# EBS_2020.net
KiCad netlist of a schematic drawn in Altium Designer
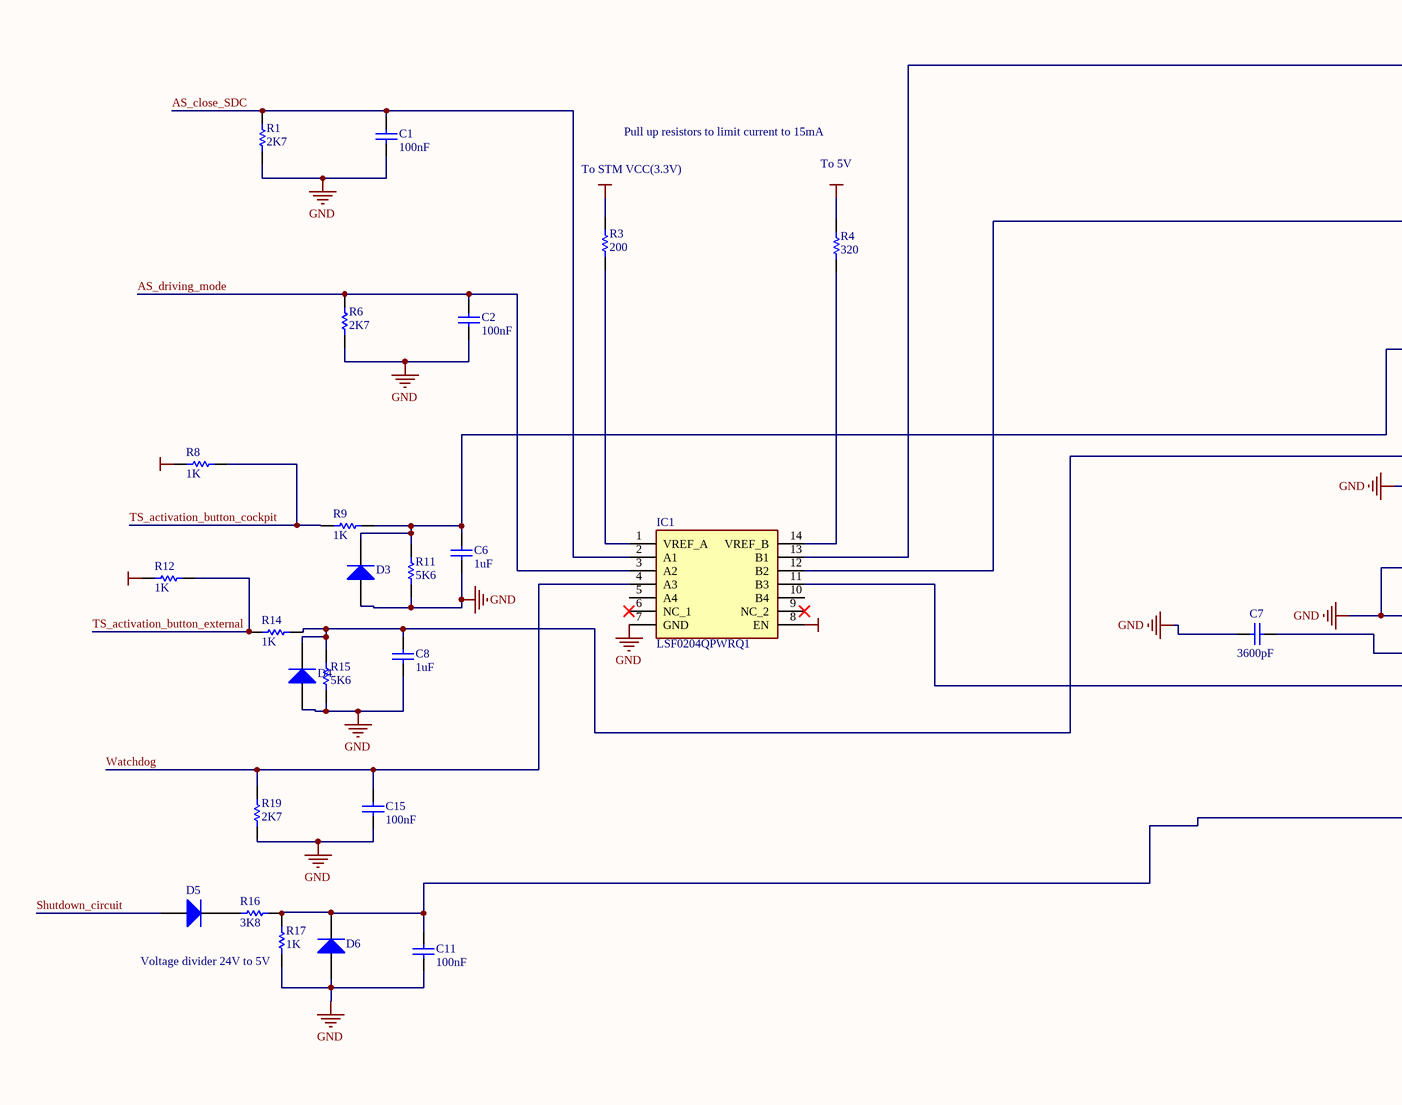
[diagram p0: EBS_2020.SchDoc, left]
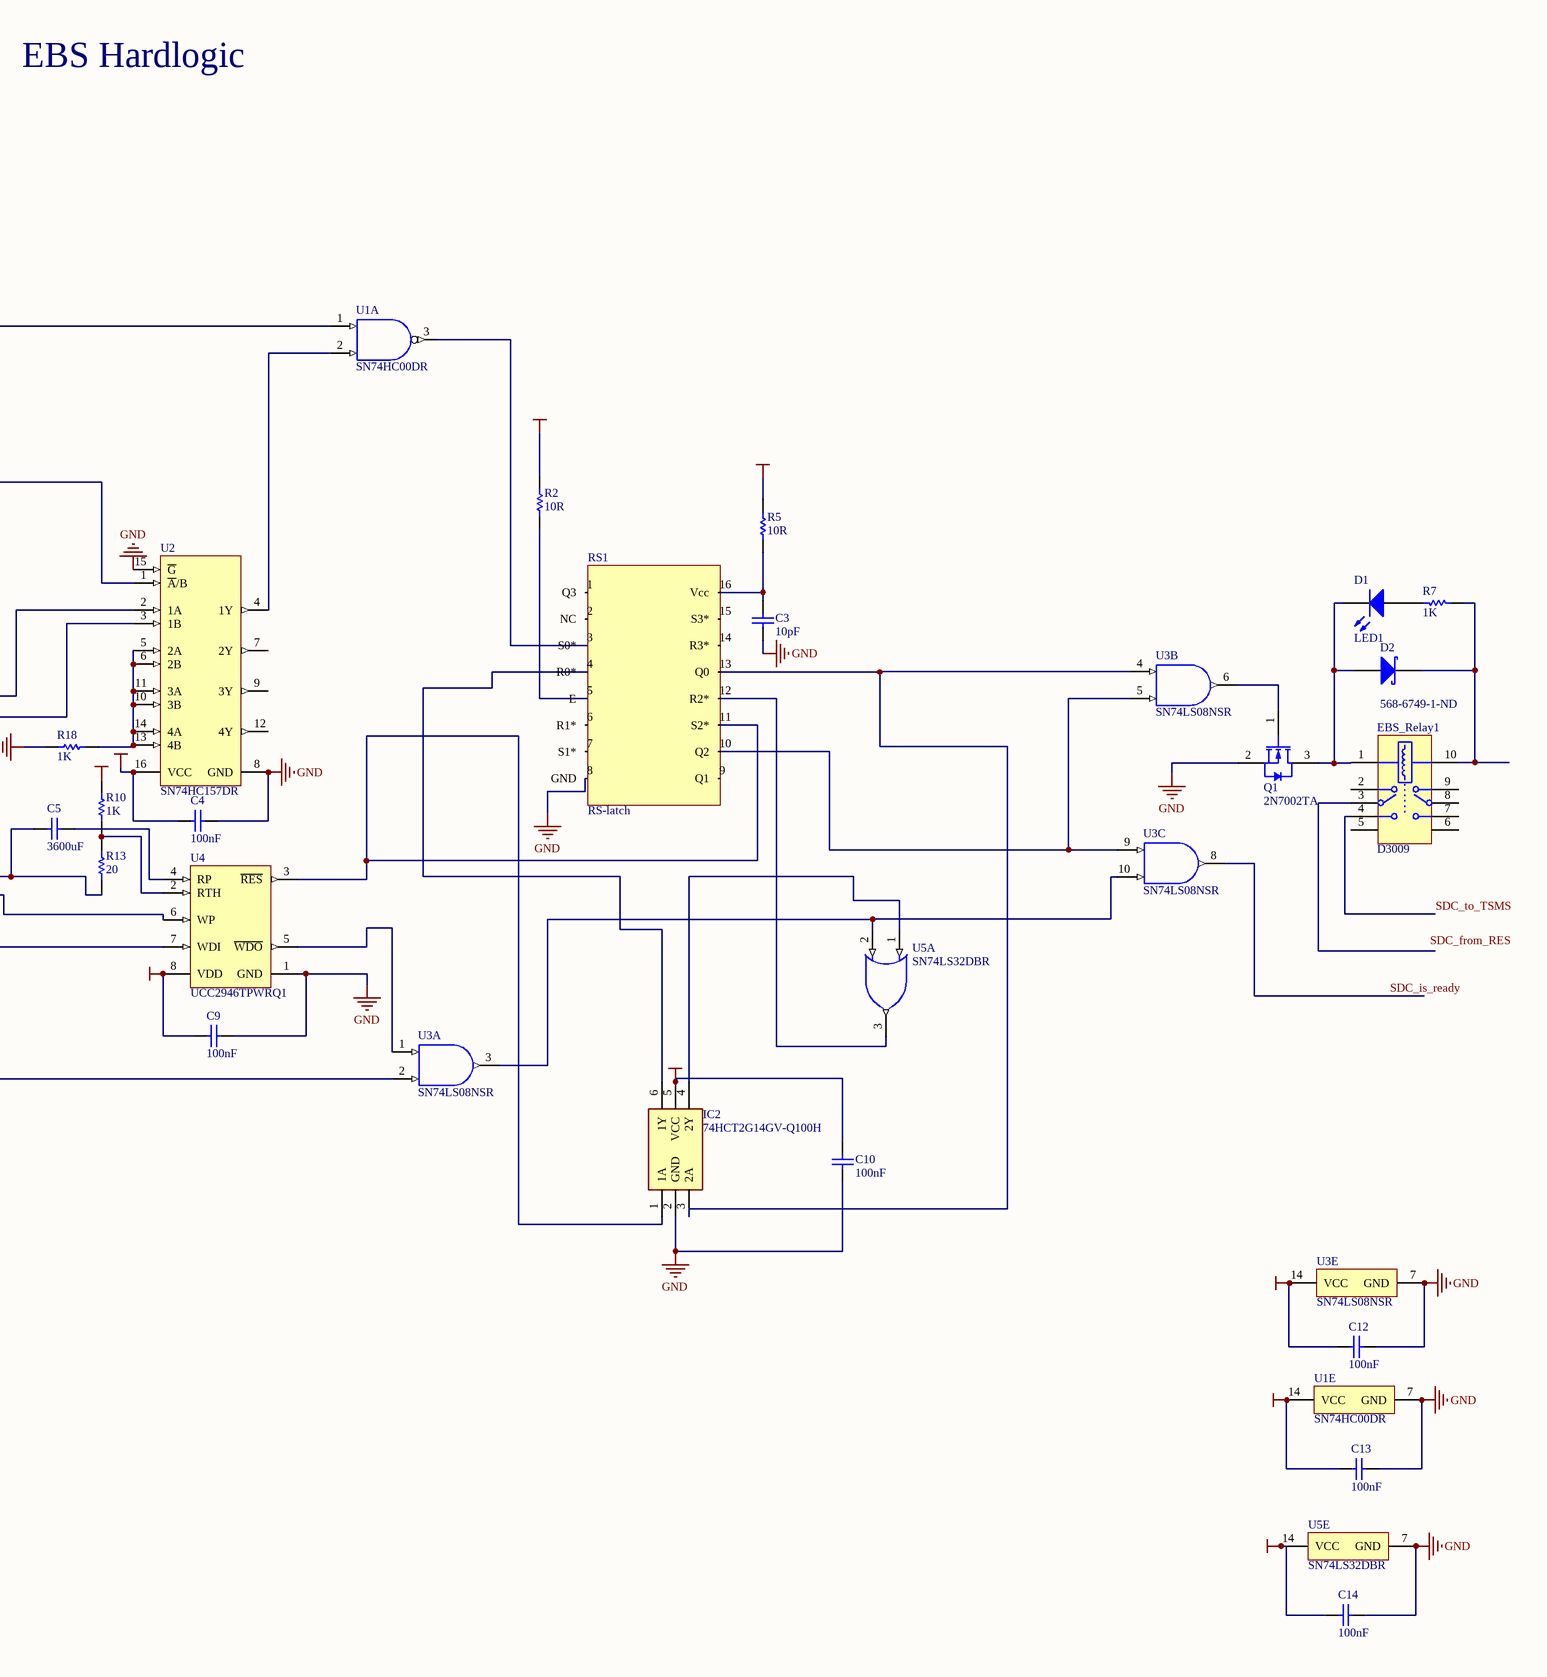
[diagram p1: EBS_2020.SchDoc, right]

(export (version "E")
  (design (tool "Eeschema 10.0.6"))
  (components
    (comp (ref "C1")
      (value "100nF")
      (footprint "SMD-0805C")
      (description "CAP 100nF 10V ±20% 0805 (2012 Metric) Thickness 0.75mm SMD")
      (fields (field (name "TOLERANCE") "Â±20%"))
      (libsource (lib "Altium Content Vault") (part "CAP"))
    )
    (comp (ref "C2")
      (value "100nF")
      (footprint "SMD-0805C")
      (description "CAP 100nF 10V ±20% 0805 (2012 Metric) Thickness 0.75mm SMD")
      (fields (field (name "TOLERANCE") "Â±20%"))
      (libsource (lib "Altium Content Vault") (part "CAP"))
    )
    (comp (ref "C3")
      (value "10pF")
      (footprint "CAPC0805(2012)100_N")
      (description "CAP 10pF 16V ±0.5pF 0805 (2012 Metric) Thickness 1mm SMD")
      (fields (field (name "TOLERANCE") "Â±0.5pF"))
      (libsource (lib "Altium Content Vault") (part "CAP"))
    )
    (comp (ref "C4")
      (value "100nF")
      (footprint "SMD-0805C")
      (description "CAP 100nF 10V ±20% 0805 (2012 Metric) Thickness 0.75mm SMD")
      (fields (field (name "TOLERANCE") "Â±20%"))
      (libsource (lib "Altium Content Vault") (part "CAP"))
    )
    (comp (ref "C5")
      (value "3600uF")
      (footprint "SMD-0805C")
      (description "CAP 100nF 10V ±20% 0805 (2012 Metric) Thickness 0.75mm SMD")
      (fields (field (name "TOLERANCE") "Â±20%"))
      (libsource (lib "Altium Content Vault") (part "CAP"))
    )
    (comp (ref "C6")
      (value "1uF")
      (footprint "SMD-0805C")
      (description "CAP 100nF 10V ±20% 0805 (2012 Metric) Thickness 0.75mm SMD")
      (fields (field (name "TOLERANCE") "Â±20%"))
      (libsource (lib "Altium Content Vault") (part "CAP"))
    )
    (comp (ref "C7")
      (value "3600pF")
      (footprint "dV_C1206")
      (fields
        (field (name "MANUFACTURER") "KEMET")
        (field (name "MANUFACTURER PART NUMBER") "C1206C362J5GACTU")
        (field (name "VOLTAGE") "50VDC")
      )
      (libsource (lib "altium-import") (part "root_2_Cap_"))
    )
    (comp (ref "C8")
      (value "1uF")
      (footprint "SMD-0805C")
      (description "CAP 100nF 10V ±20% 0805 (2012 Metric) Thickness 0.75mm SMD")
      (fields (field (name "TOLERANCE") "Â±20%"))
      (libsource (lib "Altium Content Vault") (part "CAP"))
    )
    (comp (ref "C9")
      (value "100nF")
      (footprint "SMD-0805C")
      (description "CAP 100nF 10V ±20% 0805 (2012 Metric) Thickness 0.75mm SMD")
      (fields (field (name "TOLERANCE") "Â±20%"))
      (libsource (lib "Altium Content Vault") (part "CAP"))
    )
    (comp (ref "C10")
      (value "100nF")
      (footprint "SMD-0805C")
      (description "CAP 100nF 10V ±20% 0805 (2012 Metric) Thickness 0.75mm SMD")
      (fields (field (name "TOLERANCE") "Â±20%"))
      (libsource (lib "Altium Content Vault") (part "CAP"))
    )
    (comp (ref "C11")
      (value "100nF")
      (footprint "SMD-0805C")
      (description "CAP 100nF 10V ±20% 0805 (2012 Metric) Thickness 0.75mm SMD")
      (fields (field (name "TOLERANCE") "Â±20%"))
      (libsource (lib "Altium Content Vault") (part "CAP"))
    )
    (comp (ref "C12")
      (value "100nF")
      (footprint "SMD-0805C")
      (description "CAP 100nF 10V ±20% 0805 (2012 Metric) Thickness 0.75mm SMD")
      (fields (field (name "TOLERANCE") "Â±20%"))
      (libsource (lib "Altium Content Vault") (part "CAP"))
    )
    (comp (ref "C13")
      (value "100nF")
      (footprint "SMD-0805C")
      (description "CAP 100nF 10V ±20% 0805 (2012 Metric) Thickness 0.75mm SMD")
      (fields (field (name "TOLERANCE") "Â±20%"))
      (libsource (lib "Altium Content Vault") (part "CAP"))
    )
    (comp (ref "C14")
      (value "100nF")
      (footprint "SMD-0805C")
      (description "CAP 100nF 10V ±20% 0805 (2012 Metric) Thickness 0.75mm SMD")
      (fields (field (name "TOLERANCE") "Â±20%"))
      (libsource (lib "Altium Content Vault") (part "CAP"))
    )
    (comp (ref "C15")
      (value "100nF")
      (footprint "SMD-0805C")
      (description "CAP 100nF 10V ±20% 0805 (2012 Metric) Thickness 0.75mm SMD")
      (fields (field (name "TOLERANCE") "Â±20%"))
      (libsource (lib "Altium Content Vault") (part "CAP"))
    )
    (comp (ref "D1")
      (value "LED1")
      (footprint "PcbLib1:OSRAM_0805")
      (description "Typical RED GaAs LED")
      (fields (field (name "PUBLISHER") "Altium Limited"))
      (libsource (lib "Miscellaneous Devices") (part "LED1"))
    )
    (comp (ref "D2")
      (value "~")
      (footprint "footprint NODES:1SMA12AT3G")
      (description "Schottky Diode")
      (fields
        (field (name "SUPPLIER PART NUMBER 1") "568-6749-1-ND")
        (field (name "MANUFACTURER") "NXP USA Inc.")
        (field (name "MANUFACTURER PART NUMBER") "PMEG4030ER,115")
        (field (name "PUBLISHER") "Altium Limited")
      )
      (libsource (lib "Miscellaneous Devices") (part "D Schottky"))
    )
    (comp (ref "D3")
      (value "~")
      (footprint "1SMA12AT3G")
      (description "High Conductance Fast Diode")
      (fields
        (field (name "MANUFACTURER") "PANASONIC ELECTRONIC COMPONENTS")
        (field (name "MANUFACTURER PART NUMBER") "DB2W31900L")
      )
      (libsource (lib "Miscellaneous Devices") (part "Diode 1N914"))
    )
    (comp (ref "D4")
      (value "~")
      (footprint "1SMA12AT3G")
      (description "High Conductance Fast Diode")
      (fields
        (field (name "MANUFACTURER") "PANASONIC ELECTRONIC COMPONENTS")
        (field (name "MANUFACTURER PART NUMBER") "DB2W31900L")
      )
      (libsource (lib "Miscellaneous Devices") (part "Diode 1N914"))
    )
    (comp (ref "D5")
      (value "~")
      (footprint "1SMA12AT3G")
      (description "High Conductance Fast Diode")
      (fields
        (field (name "MANUFACTURER") "PANASONIC ELECTRONIC COMPONENTS")
        (field (name "MANUFACTURER PART NUMBER") "DB2W31900L")
      )
      (libsource (lib "Miscellaneous Devices") (part "Diode 1N914"))
    )
    (comp (ref "D6")
      (value "~")
      (footprint "1SMA12AT3G")
      (description "High Conductance Fast Diode")
      (fields
        (field (name "MANUFACTURER") "PANASONIC ELECTRONIC COMPONENTS")
        (field (name "MANUFACTURER PART NUMBER") "DB2W31900L")
      )
      (libsource (lib "Miscellaneous Devices") (part "Diode 1N914"))
    )
    (comp (ref "EBS_Relay1")
      (value "D3009")
      (footprint "TE_Connectivity_D3009_0:TECO-FP2-10_V")
      (description "2 Form C, Monostable FP2 Relay, 2 A, 5 V, 10-Pin THT(FP2), RoHS, Tube")
      (fields (field (name "MANUFACTURER") "TE Connectivity"))
      (libsource (lib "TE_Connectivity_D3009") (part "D3009"))
    )
    (comp (ref "IC1")
      (value "LSF0204QPWRQ1")
      (footprint "SamacSys:SOP65P640X120-14N")
      (description "Integrated Circuit")
      (fields (field (name "MOUSER2 PART NUMBER") "595-LSF0204QPWRQ1"))
      (libsource (lib "*") (part "LSF0204QPWRQ1"))
    )
    (comp (ref "IC2")
      (value "74HCT2G14GV-Q100H")
      (footprint "SamacSys:SOT95P275X110-6N")
      (description "Integrated Circuit")
      (libsource (lib "*") (part "74HCT2G14GV-Q100H"))
    )
    (comp (ref "Q1")
      (value "2N7002TA")
      (footprint "DIOD-SOT23-3_V")
      (fields (field (name "MANUFACTURER") "DiodesIncorporated"))
      (libsource (lib "Altium Content Vault") (part "NEMOS-GSD-3"))
    )
    (comp (ref "R1")
      (value "2K7")
      (footprint "SMD-0805-RES")
      (description "2K7 0.125W 1% 0805 (2012 Metric)  SMD")
      (fields (field (name "TOLERANCE") "1 %") (field (name "POWER") "0.125 W"))
      (libsource (lib "Altium Content Vault") (part "RES"))
    )
    (comp (ref "R2")
      (value "10R")
      (footprint "RESC0805(2012)_N")
      (description "10R 0.125W 1% 0805 (2012 Metric)  SMD")
      (fields (field (name "TOLERANCE") "1 %") (field (name "POWER") "0.125 W"))
      (libsource (lib "Altium Content Vault") (part "RES"))
    )
    (comp (ref "R3")
      (value "200")
      (footprint "SMD-0805-RES")
      (description "2K7 0.125W 1% 0805 (2012 Metric)  SMD")
      (fields (field (name "TOLERANCE") "1 %") (field (name "POWER") "0.125 W"))
      (libsource (lib "Altium Content Vault") (part "RES"))
    )
    (comp (ref "R4")
      (value "320")
      (footprint "SMD-0805-RES")
      (description "2K7 0.125W 1% 0805 (2012 Metric)  SMD")
      (fields (field (name "TOLERANCE") "1 %") (field (name "POWER") "0.125 W"))
      (libsource (lib "Altium Content Vault") (part "RES"))
    )
    (comp (ref "R5")
      (value "10R")
      (footprint "RESC0805(2012)_N")
      (description "10R 0.125W 1% 0805 (2012 Metric)  SMD")
      (fields (field (name "TOLERANCE") "1 %") (field (name "POWER") "0.125 W"))
      (libsource (lib "Altium Content Vault") (part "RES"))
    )
    (comp (ref "R6")
      (value "2K7")
      (footprint "SMD-0805-RES")
      (description "2K7 0.125W 1% 0805 (2012 Metric)  SMD")
      (fields (field (name "TOLERANCE") "1 %") (field (name "POWER") "0.125 W"))
      (libsource (lib "Altium Content Vault") (part "RES"))
    )
    (comp (ref "R7")
      (value "1K")
      (footprint "SMD-0805-RES")
      (description "1K 0.125W 1% 0805 (2012 Metric)  SMD")
      (fields (field (name "TOLERANCE") "1 %") (field (name "POWER") "0.125 W"))
      (libsource (lib "Altium Content Vault") (part "RES"))
    )
    (comp (ref "R8")
      (value "1K")
      (footprint "SMD-0805-RES")
      (description "2K7 0.125W 1% 0805 (2012 Metric)  SMD")
      (fields (field (name "TOLERANCE") "1 %") (field (name "POWER") "0.125 W"))
      (libsource (lib "Altium Content Vault") (part "RES"))
    )
    (comp (ref "R9")
      (value "1K")
      (footprint "SMD-0805-RES")
      (description "2K7 0.125W 1% 0805 (2012 Metric)  SMD")
      (fields (field (name "TOLERANCE") "1 %") (field (name "POWER") "0.125 W"))
      (libsource (lib "Altium Content Vault") (part "RES"))
    )
    (comp (ref "R10")
      (value "1K")
      (footprint "SMD-0805-RES")
      (description "2K7 0.125W 1% 0805 (2012 Metric)  SMD")
      (fields (field (name "TOLERANCE") "1 %") (field (name "POWER") "0.125 W"))
      (libsource (lib "Altium Content Vault") (part "RES"))
    )
    (comp (ref "R11")
      (value "5K6")
      (footprint "SMD-0805-RES")
      (description "2K7 0.125W 1% 0805 (2012 Metric)  SMD")
      (fields (field (name "TOLERANCE") "1 %") (field (name "POWER") "0.125 W"))
      (libsource (lib "Altium Content Vault") (part "RES"))
    )
    (comp (ref "R12")
      (value "1K")
      (footprint "SMD-0805-RES")
      (description "2K7 0.125W 1% 0805 (2012 Metric)  SMD")
      (fields (field (name "TOLERANCE") "1 %") (field (name "POWER") "0.125 W"))
      (libsource (lib "Altium Content Vault") (part "RES"))
    )
    (comp (ref "R13")
      (value "20")
      (footprint "SMD-0805-RES")
      (description "2K7 0.125W 1% 0805 (2012 Metric)  SMD")
      (fields (field (name "TOLERANCE") "1 %") (field (name "POWER") "0.125 W"))
      (libsource (lib "Altium Content Vault") (part "RES"))
    )
    (comp (ref "R14")
      (value "1K")
      (footprint "SMD-0805-RES")
      (description "2K7 0.125W 1% 0805 (2012 Metric)  SMD")
      (fields (field (name "TOLERANCE") "1 %") (field (name "POWER") "0.125 W"))
      (libsource (lib "Altium Content Vault") (part "RES"))
    )
    (comp (ref "R15")
      (value "5K6")
      (footprint "SMD-0805-RES")
      (description "2K7 0.125W 1% 0805 (2012 Metric)  SMD")
      (fields (field (name "TOLERANCE") "1 %") (field (name "POWER") "0.125 W"))
      (libsource (lib "Altium Content Vault") (part "RES"))
    )
    (comp (ref "R16")
      (value "3K8")
      (footprint "SMD-0805-RES")
      (description "2K7 0.125W 1% 0805 (2012 Metric)  SMD")
      (fields (field (name "TOLERANCE") "1 %") (field (name "POWER") "0.125 W"))
      (libsource (lib "Altium Content Vault") (part "RES"))
    )
    (comp (ref "R17")
      (value "1K")
      (footprint "SMD-0805-RES")
      (description "2K7 0.125W 1% 0805 (2012 Metric)  SMD")
      (fields (field (name "TOLERANCE") "1 %") (field (name "POWER") "0.125 W"))
      (libsource (lib "Altium Content Vault") (part "RES"))
    )
    (comp (ref "R18")
      (value "1K")
      (footprint "SMD-0805-RES")
      (description "2K7 0.125W 1% 0805 (2012 Metric)  SMD")
      (fields (field (name "TOLERANCE") "1 %") (field (name "POWER") "0.125 W"))
      (libsource (lib "Altium Content Vault") (part "RES"))
    )
    (comp (ref "R19")
      (value "2K7")
      (footprint "SMD-0805-RES")
      (description "2K7 0.125W 1% 0805 (2012 Metric)  SMD")
      (fields (field (name "TOLERANCE") "1 %") (field (name "POWER") "0.125 W"))
      (libsource (lib "Altium Content Vault") (part "RES"))
    )
    (comp (ref "RS1")
      (value "RS-latch")
      (footprint "SOIC127P600X175-16N:SOIC127P600X175-16N")
      (description "MC14044B")
      (libsource (lib "BSPDLib") (part "RS-latch"))
    )
    (comp (ref "U1")
      (value "SN74HC00DR")
      (footprint "D0014A_M")
      (description "Quad 2-Input Positive-NAND Gates, D0014A, LARGE T&R")
      (fields
        (field (name "GENERIC PART NUMBER") "SN74HC00")
        (field (name "MANUFACTURER") "Texas Instruments")
      )
      (libsource (lib "Altium Content Vault") (part "TI-NAND-4-2IN-14_G"))
    )
    (comp (ref "U2")
      (value "SN74HC157DR")
      (footprint "D0016A_M")
      (description "Quadruple 2-Line To 1-Line Data Selectors/Multiplexers, D0016A, LARGE T&R")
      (fields
        (field (name "MANUFACTURER") "Texas Instruments")
        (field (name "GENERIC PART NUMBER") "SN74HC157")
      )
      (libsource (lib "Altium Content Vault") (part "TI-XXX4XXXX15XX-16"))
    )
    (comp (ref "U3")
      (value "SN74LS08NSR")
      (footprint "NS0014A_L")
      (description "Quadruple 2-Input Positive-AND Gates, NS0014A, LARGE T&R")
      (fields
        (field (name "MANUFACTURER") "Texas Instruments")
        (field (name "GENERIC PART NUMBER") "SN74LS08")
      )
      (libsource (lib "Altium Content Vault") (part "TI-AND-4-2IN-14"))
    )
    (comp (ref "U4")
      (value "UCC2946TPWRQ1")
      (footprint "PW8_N")
      (fields (field (name "MANUFACTURER") "Texas Instruments"))
      (libsource (lib "TI Power Management Supervisor and Reset IC") (part "UCC2946TPWRQ1"))
    )
    (comp (ref "U5")
      (value "SN74LS32DBR")
      (footprint "DB0014A_N")
      (description "Quad 2-input positive-OR gates, DB0014A, LARGE T&R")
      (fields
        (field (name "GENERIC PART NUMBER") "SN74LS32")
        (field (name "MANUFACTURER") "Texas Instruments")
      )
      (libsource (lib "") (part "TI-OR-4-2IN-14_1"))
    )
  )
  (nets
    (net (code "1") (name "/AS_close_SDC") (class "Default")
      (node (ref "C1") (pin "2") (pinfunction "2_2") (pintype "passive"))
      (node (ref "IC1") (pin "2") (pinfunction "A1_2") (pintype "passive"))
      (node (ref "R1") (pin "2") (pinfunction "2_2") (pintype "passive"))
    )
    (net (code "2") (name "/AS_driving_mode") (class "Default")
      (node (ref "C2") (pin "2") (pinfunction "2_2") (pintype "passive"))
      (node (ref "IC1") (pin "3") (pinfunction "A2_3") (pintype "passive"))
      (node (ref "R6") (pin "2") (pinfunction "2_2") (pintype "passive"))
    )
    (net (code "4") (name "/SDC_is_ready") (class "Default")
      (node (ref "U3") (pin "8") (pinfunction "3Y_8") (pintype "output"))
    )
    (net (code "5") (name "/SDC_to_TSMS") (class "Default")
      (node (ref "EBS_Relay1") (pin "4") (pinfunction "4_4") (pintype "passive"))
    )
    (net (code "6") (name "/Shutdown_circuit") (class "Default")
      (node (ref "D5") (pin "1") (pinfunction "A_1") (pintype "passive"))
    )
    (net (code "7") (name "/TS_activation_button_cockpit") (class "Default")
      (node (ref "R8") (pin "1") (pinfunction "1_1") (pintype "passive"))
      (node (ref "R9") (pin "2") (pinfunction "2_2") (pintype "passive"))
    )
    (net (code "8") (name "/TS_activation_button_external") (class "Default")
      (node (ref "R12") (pin "1") (pinfunction "1_1") (pintype "passive"))
      (node (ref "R14") (pin "2") (pinfunction "2_2") (pintype "passive"))
    )
    (net (code "9") (name "/Watchdog") (class "Default")
      (node (ref "C15") (pin "2") (pinfunction "2_2") (pintype "passive"))
      (node (ref "IC1") (pin "4") (pinfunction "A3_4") (pintype "passive"))
      (node (ref "R19") (pin "2") (pinfunction "2_2") (pintype "passive"))
    )
    (net (code "10") (name "<NO NET>") (class "Default")
      (node (ref "C10") (pin "1") (pinfunction "1_1") (pintype "passive"))
      (node (ref "C12") (pin "2") (pinfunction "2_2") (pintype "passive"))
      (node (ref "C13") (pin "2") (pinfunction "2_2") (pintype "passive"))
      (node (ref "C14") (pin "2") (pinfunction "2_2") (pintype "passive"))
      (node (ref "C4") (pin "2") (pinfunction "2_2") (pintype "passive"))
      (node (ref "C9") (pin "2") (pinfunction "2_2") (pintype "passive"))
      (node (ref "IC1") (pin "8") (pinfunction "EN_8") (pintype "passive"))
      (node (ref "IC2") (pin "5") (pinfunction "VCC_5") (pintype "passive"))
      (node (ref "R10") (pin "2") (pinfunction "2_2") (pintype "passive"))
      (node (ref "R12") (pin "2") (pinfunction "2_2") (pintype "passive"))
      (node (ref "R2") (pin "2") (pinfunction "2_2") (pintype "passive"))
      (node (ref "R3") (pin "1") (pinfunction "1_1") (pintype "passive"))
      (node (ref "R4") (pin "1") (pinfunction "1_1") (pintype "passive"))
      (node (ref "R5") (pin "2") (pinfunction "2_2") (pintype "passive"))
      (node (ref "R8") (pin "2") (pinfunction "2_2") (pintype "passive"))
      (node (ref "U1") (pin "14") (pinfunction "VCC_14") (pintype "power_in"))
      (node (ref "U2") (pin "16") (pinfunction "VCC_16") (pintype "power_in"))
      (node (ref "U3") (pin "14") (pinfunction "VCC_14") (pintype "power_in"))
      (node (ref "U4") (pin "8") (pinfunction "VDD_8") (pintype "power_in"))
      (node (ref "U5") (pin "14") (pinfunction "VCC_14") (pintype "power_in"))
    )
    (net (code "11") (name "GND") (class "Default")
      (node (ref "C1") (pin "1") (pinfunction "1_1") (pintype "passive"))
      (node (ref "C10") (pin "2") (pinfunction "2_2") (pintype "passive"))
      (node (ref "C11") (pin "1") (pinfunction "1_1") (pintype "passive"))
      (node (ref "C12") (pin "1") (pinfunction "1_1") (pintype "passive"))
      (node (ref "C13") (pin "1") (pinfunction "1_1") (pintype "passive"))
      (node (ref "C14") (pin "1") (pinfunction "1_1") (pintype "passive"))
      (node (ref "C15") (pin "1") (pinfunction "1_1") (pintype "passive"))
      (node (ref "C2") (pin "1") (pinfunction "1_1") (pintype "passive"))
      (node (ref "C3") (pin "1") (pinfunction "1_1") (pintype "passive"))
      (node (ref "C4") (pin "1") (pinfunction "1_1") (pintype "passive"))
      (node (ref "C5") (pin "2") (pinfunction "2_2") (pintype "passive"))
      (node (ref "C6") (pin "1") (pinfunction "1_1") (pintype "passive"))
      (node (ref "C7") (pin "2") (pinfunction "2_2") (pintype "passive"))
      (node (ref "C8") (pin "1") (pinfunction "1_1") (pintype "passive"))
      (node (ref "C9") (pin "1") (pinfunction "1_1") (pintype "passive"))
      (node (ref "D3") (pin "1") (pinfunction "A_1") (pintype "passive"))
      (node (ref "D4") (pin "1") (pinfunction "A_1") (pintype "passive"))
      (node (ref "D6") (pin "1") (pinfunction "A_1") (pintype "passive"))
      (node (ref "IC1") (pin "7") (pinfunction "GND_7") (pintype "passive"))
      (node (ref "IC2") (pin "2") (pinfunction "GND_2") (pintype "passive"))
      (node (ref "Q1") (pin "2") (pinfunction "S_2") (pintype "passive"))
      (node (ref "R1") (pin "1") (pinfunction "1_1") (pintype "passive"))
      (node (ref "R11") (pin "2") (pinfunction "2_2") (pintype "passive"))
      (node (ref "R13") (pin "1") (pinfunction "1_1") (pintype "passive"))
      (node (ref "R15") (pin "2") (pinfunction "2_2") (pintype "passive"))
      (node (ref "R17") (pin "1") (pinfunction "1_1") (pintype "passive"))
      (node (ref "R18") (pin "2") (pinfunction "2_2") (pintype "passive"))
      (node (ref "R19") (pin "1") (pinfunction "1_1") (pintype "passive"))
      (node (ref "R6") (pin "1") (pinfunction "1_1") (pintype "passive"))
      (node (ref "RS1") (pin "8") (pinfunction "GND_8") (pintype "passive"))
      (node (ref "U1") (pin "7") (pinfunction "GND_7") (pintype "power_in"))
      (node (ref "U2") (pin "15") (pinfunction "~{G}_15") (pintype "input"))
      (node (ref "U2") (pin "8") (pinfunction "GND_8") (pintype "power_in"))
      (node (ref "U3") (pin "7") (pinfunction "GND_7") (pintype "power_in"))
      (node (ref "U4") (pin "1") (pinfunction "GND_1") (pintype "power_in"))
      (node (ref "U5") (pin "7") (pinfunction "GND_7") (pintype "power_in"))
    )
    (net (code "12") (name "Net-(D1-A)") (class "Default")
      (node (ref "D1") (pin "1") (pinfunction "A_1") (pintype "passive"))
      (node (ref "R7") (pin "2") (pinfunction "2_2") (pintype "passive"))
    )
    (net (code "13") (name "Net-(D1-K)") (class "Default")
      (node (ref "D1") (pin "2") (pinfunction "K_2") (pintype "passive"))
      (node (ref "D2") (pin "1") (pinfunction "A_1") (pintype "passive"))
      (node (ref "EBS_Relay1") (pin "1") (pinfunction "1_1") (pintype "passive"))
      (node (ref "Q1") (pin "3") (pinfunction "D_3") (pintype "passive"))
    )
    (net (code "14") (name "Net-(D2-K)") (class "Default")
      (node (ref "D2") (pin "2") (pinfunction "K_2") (pintype "passive"))
      (node (ref "EBS_Relay1") (pin "10") (pinfunction "10_10") (pintype "passive"))
      (node (ref "R7") (pin "1") (pinfunction "1_1") (pintype "passive"))
    )
    (net (code "15") (name "Net-(D3-K)") (class "Default")
      (node (ref "C6") (pin "2") (pinfunction "2_2") (pintype "passive"))
      (node (ref "D3") (pin "2") (pinfunction "K_2") (pintype "passive"))
      (node (ref "R11") (pin "1") (pinfunction "1_1") (pintype "passive"))
      (node (ref "R9") (pin "1") (pinfunction "1_1") (pintype "passive"))
      (node (ref "U2") (pin "2") (pinfunction "1A_2") (pintype "input"))
    )
    (net (code "16") (name "Net-(D4-K)") (class "Default")
      (node (ref "C8") (pin "2") (pinfunction "2_2") (pintype "passive"))
      (node (ref "D4") (pin "2") (pinfunction "K_2") (pintype "passive"))
      (node (ref "R14") (pin "1") (pinfunction "1_1") (pintype "passive"))
      (node (ref "R15") (pin "1") (pinfunction "1_1") (pintype "passive"))
      (node (ref "U2") (pin "3") (pinfunction "1B_3") (pintype "input"))
    )
    (net (code "17") (name "Net-(D5-K)") (class "Default")
      (node (ref "D5") (pin "2") (pinfunction "K_2") (pintype "passive"))
      (node (ref "R16") (pin "2") (pinfunction "2_2") (pintype "passive"))
    )
    (net (code "18") (name "Net-(D6-K)") (class "Default")
      (node (ref "C11") (pin "2") (pinfunction "2_2") (pintype "passive"))
      (node (ref "D6") (pin "2") (pinfunction "K_2") (pintype "passive"))
      (node (ref "R16") (pin "1") (pinfunction "1_1") (pintype "passive"))
      (node (ref "R17") (pin "2") (pinfunction "2_2") (pintype "passive"))
      (node (ref "U3") (pin "2") (pinfunction "1B_2") (pintype "input"))
    )
    (net (code "19") (name "Net-(IC1-B1)") (class "Default")
      (node (ref "IC1") (pin "13") (pinfunction "B1_13") (pintype "passive"))
      (node (ref "U1") (pin "1") (pinfunction "1A_1") (pintype "input"))
    )
    (net (code "20") (name "Net-(IC1-B2)") (class "Default")
      (node (ref "IC1") (pin "12") (pinfunction "B2_12") (pintype "passive"))
      (node (ref "U2") (pin "1") (pinfunction "~{A}/B_1") (pintype "input"))
    )
    (net (code "21") (name "Net-(IC1-B3)") (class "Default")
      (node (ref "IC1") (pin "11") (pinfunction "B3_11") (pintype "passive"))
      (node (ref "U4") (pin "7") (pinfunction "WDI_7") (pintype "input"))
    )
    (net (code "22") (name "Net-(IC1-VREF_A)") (class "Default")
      (node (ref "IC1") (pin "1") (pinfunction "VREF_A_1") (pintype "passive"))
      (node (ref "R3") (pin "2") (pinfunction "2_2") (pintype "passive"))
    )
    (net (code "23") (name "Net-(IC1-VREF_B)") (class "Default")
      (node (ref "IC1") (pin "14") (pinfunction "VREF_B_14") (pintype "passive"))
      (node (ref "R4") (pin "2") (pinfunction "2_2") (pintype "passive"))
    )
    (net (code "24") (name "Net-(IC2-1A)") (class "Default")
      (node (ref "IC2") (pin "1") (pinfunction "1A_1") (pintype "passive"))
      (node (ref "RS1") (pin "11") (pinfunction "S2*_11") (pintype "passive"))
      (node (ref "U4") (pin "3") (pinfunction "~{RES}_3") (pintype "output"))
    )
    (net (code "25") (name "Net-(IC2-1Y)") (class "Default")
      (node (ref "IC2") (pin "6") (pinfunction "1Y_6") (pintype "passive"))
      (node (ref "RS1") (pin "4") (pinfunction "R0*_4") (pintype "passive"))
    )
    (net (code "26") (name "Net-(IC2-2A)") (class "Default")
      (node (ref "IC2") (pin "3") (pinfunction "2A_3") (pintype "passive"))
      (node (ref "RS1") (pin "13") (pinfunction "Q0_13") (pintype "passive"))
      (node (ref "U3") (pin "4") (pinfunction "2A_4") (pintype "input"))
    )
    (net (code "27") (name "Net-(IC2-2Y)") (class "Default")
      (node (ref "IC2") (pin "4") (pinfunction "2Y_4") (pintype "passive"))
      (node (ref "U5") (pin "1") (pinfunction "1A_1") (pintype "input"))
    )
    (net (code "28") (name "Net-(Q1-G)") (class "Default")
      (node (ref "Q1") (pin "1") (pinfunction "G_1") (pintype "passive"))
      (node (ref "U3") (pin "6") (pinfunction "2Y_6") (pintype "output"))
    )
    (net (code "29") (name "Net-(RS1-E)") (class "Default")
      (node (ref "R2") (pin "1") (pinfunction "1_1") (pintype "passive"))
      (node (ref "RS1") (pin "5") (pinfunction "E_5") (pintype "passive"))
    )
    (net (code "30") (name "Net-(RS1-Q2)") (class "Default")
      (node (ref "RS1") (pin "10") (pinfunction "Q2_10") (pintype "passive"))
      (node (ref "U3") (pin "5") (pinfunction "2B_5") (pintype "input"))
      (node (ref "U3") (pin "9") (pinfunction "3A_9") (pintype "input"))
    )
    (net (code "31") (name "Net-(RS1-R2*)") (class "Default")
      (node (ref "RS1") (pin "12") (pinfunction "R2*_12") (pintype "passive"))
      (node (ref "U5") (pin "3") (pinfunction "1Y_3") (pintype "output"))
    )
    (net (code "32") (name "Net-(RS1-S0*)") (class "Default")
      (node (ref "RS1") (pin "3") (pinfunction "S0*_3") (pintype "passive"))
      (node (ref "U1") (pin "3") (pinfunction "1Y_3") (pintype "output"))
    )
    (net (code "33") (name "Net-(RS1-Vcc)") (class "Default")
      (node (ref "C3") (pin "2") (pinfunction "2_2") (pintype "passive"))
      (node (ref "R5") (pin "1") (pinfunction "1_1") (pintype "passive"))
      (node (ref "RS1") (pin "16") (pinfunction "Vcc_16") (pintype "passive"))
    )
    (net (code "34") (name "Net-(U1A-1B)") (class "Default")
      (node (ref "U1") (pin "2") (pinfunction "1B_2") (pintype "input"))
      (node (ref "U2") (pin "4") (pinfunction "1Y_4") (pintype "output"))
    )
    (net (code "35") (name "Net-(U2-2A)") (class "Default")
      (node (ref "R18") (pin "1") (pinfunction "1_1") (pintype "passive"))
      (node (ref "U2") (pin "10") (pinfunction "3B_10") (pintype "input"))
      (node (ref "U2") (pin "11") (pinfunction "3A_11") (pintype "input"))
      (node (ref "U2") (pin "13") (pinfunction "4B_13") (pintype "input"))
      (node (ref "U2") (pin "14") (pinfunction "4A_14") (pintype "input"))
      (node (ref "U2") (pin "5") (pinfunction "2A_5") (pintype "input"))
      (node (ref "U2") (pin "6") (pinfunction "2B_6") (pintype "input"))
    )
    (net (code "36") (name "Net-(U3A-1A)") (class "Default")
      (node (ref "U3") (pin "1") (pinfunction "1A_1") (pintype "input"))
      (node (ref "U4") (pin "5") (pinfunction "~{WDO}_5") (pintype "output"))
    )
    (net (code "37") (name "Net-(U3A-1Y)") (class "Default")
      (node (ref "U3") (pin "10") (pinfunction "3B_10") (pintype "input"))
      (node (ref "U3") (pin "3") (pinfunction "1Y_3") (pintype "output"))
      (node (ref "U5") (pin "2") (pinfunction "1B_2") (pintype "input"))
    )
    (net (code "38") (name "Net-(U4-RP)") (class "Default")
      (node (ref "C5") (pin "1") (pinfunction "1_1") (pintype "passive"))
      (node (ref "U4") (pin "4") (pinfunction "RP_4") (pintype "input"))
    )
    (net (code "39") (name "Net-(U4-RTH)") (class "Default")
      (node (ref "R10") (pin "1") (pinfunction "1_1") (pintype "passive"))
      (node (ref "R13") (pin "2") (pinfunction "2_2") (pintype "passive"))
      (node (ref "U4") (pin "2") (pinfunction "RTH_2") (pintype "input"))
    )
    (net (code "40") (name "Net-(U4-WP)") (class "Default")
      (node (ref "C7") (pin "1") (pinfunction "1_1") (pintype "passive"))
      (node (ref "U4") (pin "6") (pinfunction "WP_6") (pintype "input"))
    )
    (net (code "41") (name "unconnected-(EBS_Relay1-Pad2)") (class "Default")
      (node (ref "EBS_Relay1") (pin "2") (pinfunction "2_2") (pintype "passive"))
    )
    (net (code "42") (name "unconnected-(EBS_Relay1-Pad3)") (class "Default")
      (node (ref "EBS_Relay1") (pin "3") (pinfunction "3_3") (pintype "passive"))
    )
    (net (code "43") (name "unconnected-(EBS_Relay1-Pad5)") (class "Default")
      (node (ref "EBS_Relay1") (pin "5") (pinfunction "5_5") (pintype "passive"))
    )
    (net (code "44") (name "unconnected-(EBS_Relay1-Pad6)") (class "Default")
      (node (ref "EBS_Relay1") (pin "6") (pinfunction "6_6") (pintype "passive"))
    )
    (net (code "45") (name "unconnected-(EBS_Relay1-Pad7)") (class "Default")
      (node (ref "EBS_Relay1") (pin "7") (pinfunction "7_7") (pintype "passive"))
    )
    (net (code "46") (name "unconnected-(EBS_Relay1-Pad8)") (class "Default")
      (node (ref "EBS_Relay1") (pin "8") (pinfunction "8_8") (pintype "passive"))
    )
    (net (code "47") (name "unconnected-(EBS_Relay1-Pad9)") (class "Default")
      (node (ref "EBS_Relay1") (pin "9") (pinfunction "9_9") (pintype "passive"))
    )
    (net (code "48") (name "unconnected-(IC1-A4-Pad5)") (class "Default")
      (node (ref "IC1") (pin "5") (pinfunction "A4_5") (pintype "passive"))
    )
    (net (code "49") (name "unconnected-(IC1-B4-Pad10)") (class "Default")
      (node (ref "IC1") (pin "10") (pinfunction "B4_10") (pintype "passive"))
    )
    (net (code "50") (name "unconnected-(IC1-NC_1-Pad6)") (class "Default")
      (node (ref "IC1") (pin "6") (pinfunction "NC_1_6") (pintype "passive+no_connect"))
    )
    (net (code "51") (name "unconnected-(IC1-NC_2-Pad9)") (class "Default")
      (node (ref "IC1") (pin "9") (pinfunction "NC_2_9") (pintype "passive+no_connect"))
    )
    (net (code "52") (name "unconnected-(RS1-NC-Pad2)") (class "Default")
      (node (ref "RS1") (pin "2") (pinfunction "NC_2") (pintype "passive"))
    )
    (net (code "53") (name "unconnected-(RS1-Q1-Pad9)") (class "Default")
      (node (ref "RS1") (pin "9") (pinfunction "Q1_9") (pintype "passive"))
    )
    (net (code "54") (name "unconnected-(RS1-Q3-Pad1)") (class "Default")
      (node (ref "RS1") (pin "1") (pinfunction "Q3_1") (pintype "passive"))
    )
    (net (code "55") (name "unconnected-(RS1-R1*-Pad6)") (class "Default")
      (node (ref "RS1") (pin "6") (pinfunction "R1*_6") (pintype "passive"))
    )
    (net (code "56") (name "unconnected-(RS1-R3*-Pad14)") (class "Default")
      (node (ref "RS1") (pin "14") (pinfunction "R3*_14") (pintype "passive"))
    )
    (net (code "57") (name "unconnected-(RS1-S1*-Pad7)") (class "Default")
      (node (ref "RS1") (pin "7") (pinfunction "S1*_7") (pintype "passive"))
    )
    (net (code "58") (name "unconnected-(RS1-S3*-Pad15)") (class "Default")
      (node (ref "RS1") (pin "15") (pinfunction "S3*_15") (pintype "passive"))
    )
    (net (code "59") (name "unconnected-(U2-2Y-Pad7)") (class "Default")
      (node (ref "U2") (pin "7") (pinfunction "2Y_7") (pintype "output"))
    )
    (net (code "60") (name "unconnected-(U2-3Y-Pad9)") (class "Default")
      (node (ref "U2") (pin "9") (pinfunction "3Y_9") (pintype "output"))
    )
    (net (code "61") (name "unconnected-(U2-4Y-Pad12)") (class "Default")
      (node (ref "U2") (pin "12") (pinfunction "4Y_12") (pintype "output"))
    )
  )
)
